# EVK-IRIS-W1-FC2_FC3_FC14_RMII.net
KiCad netlist of a schematic drawn in Altium Designer
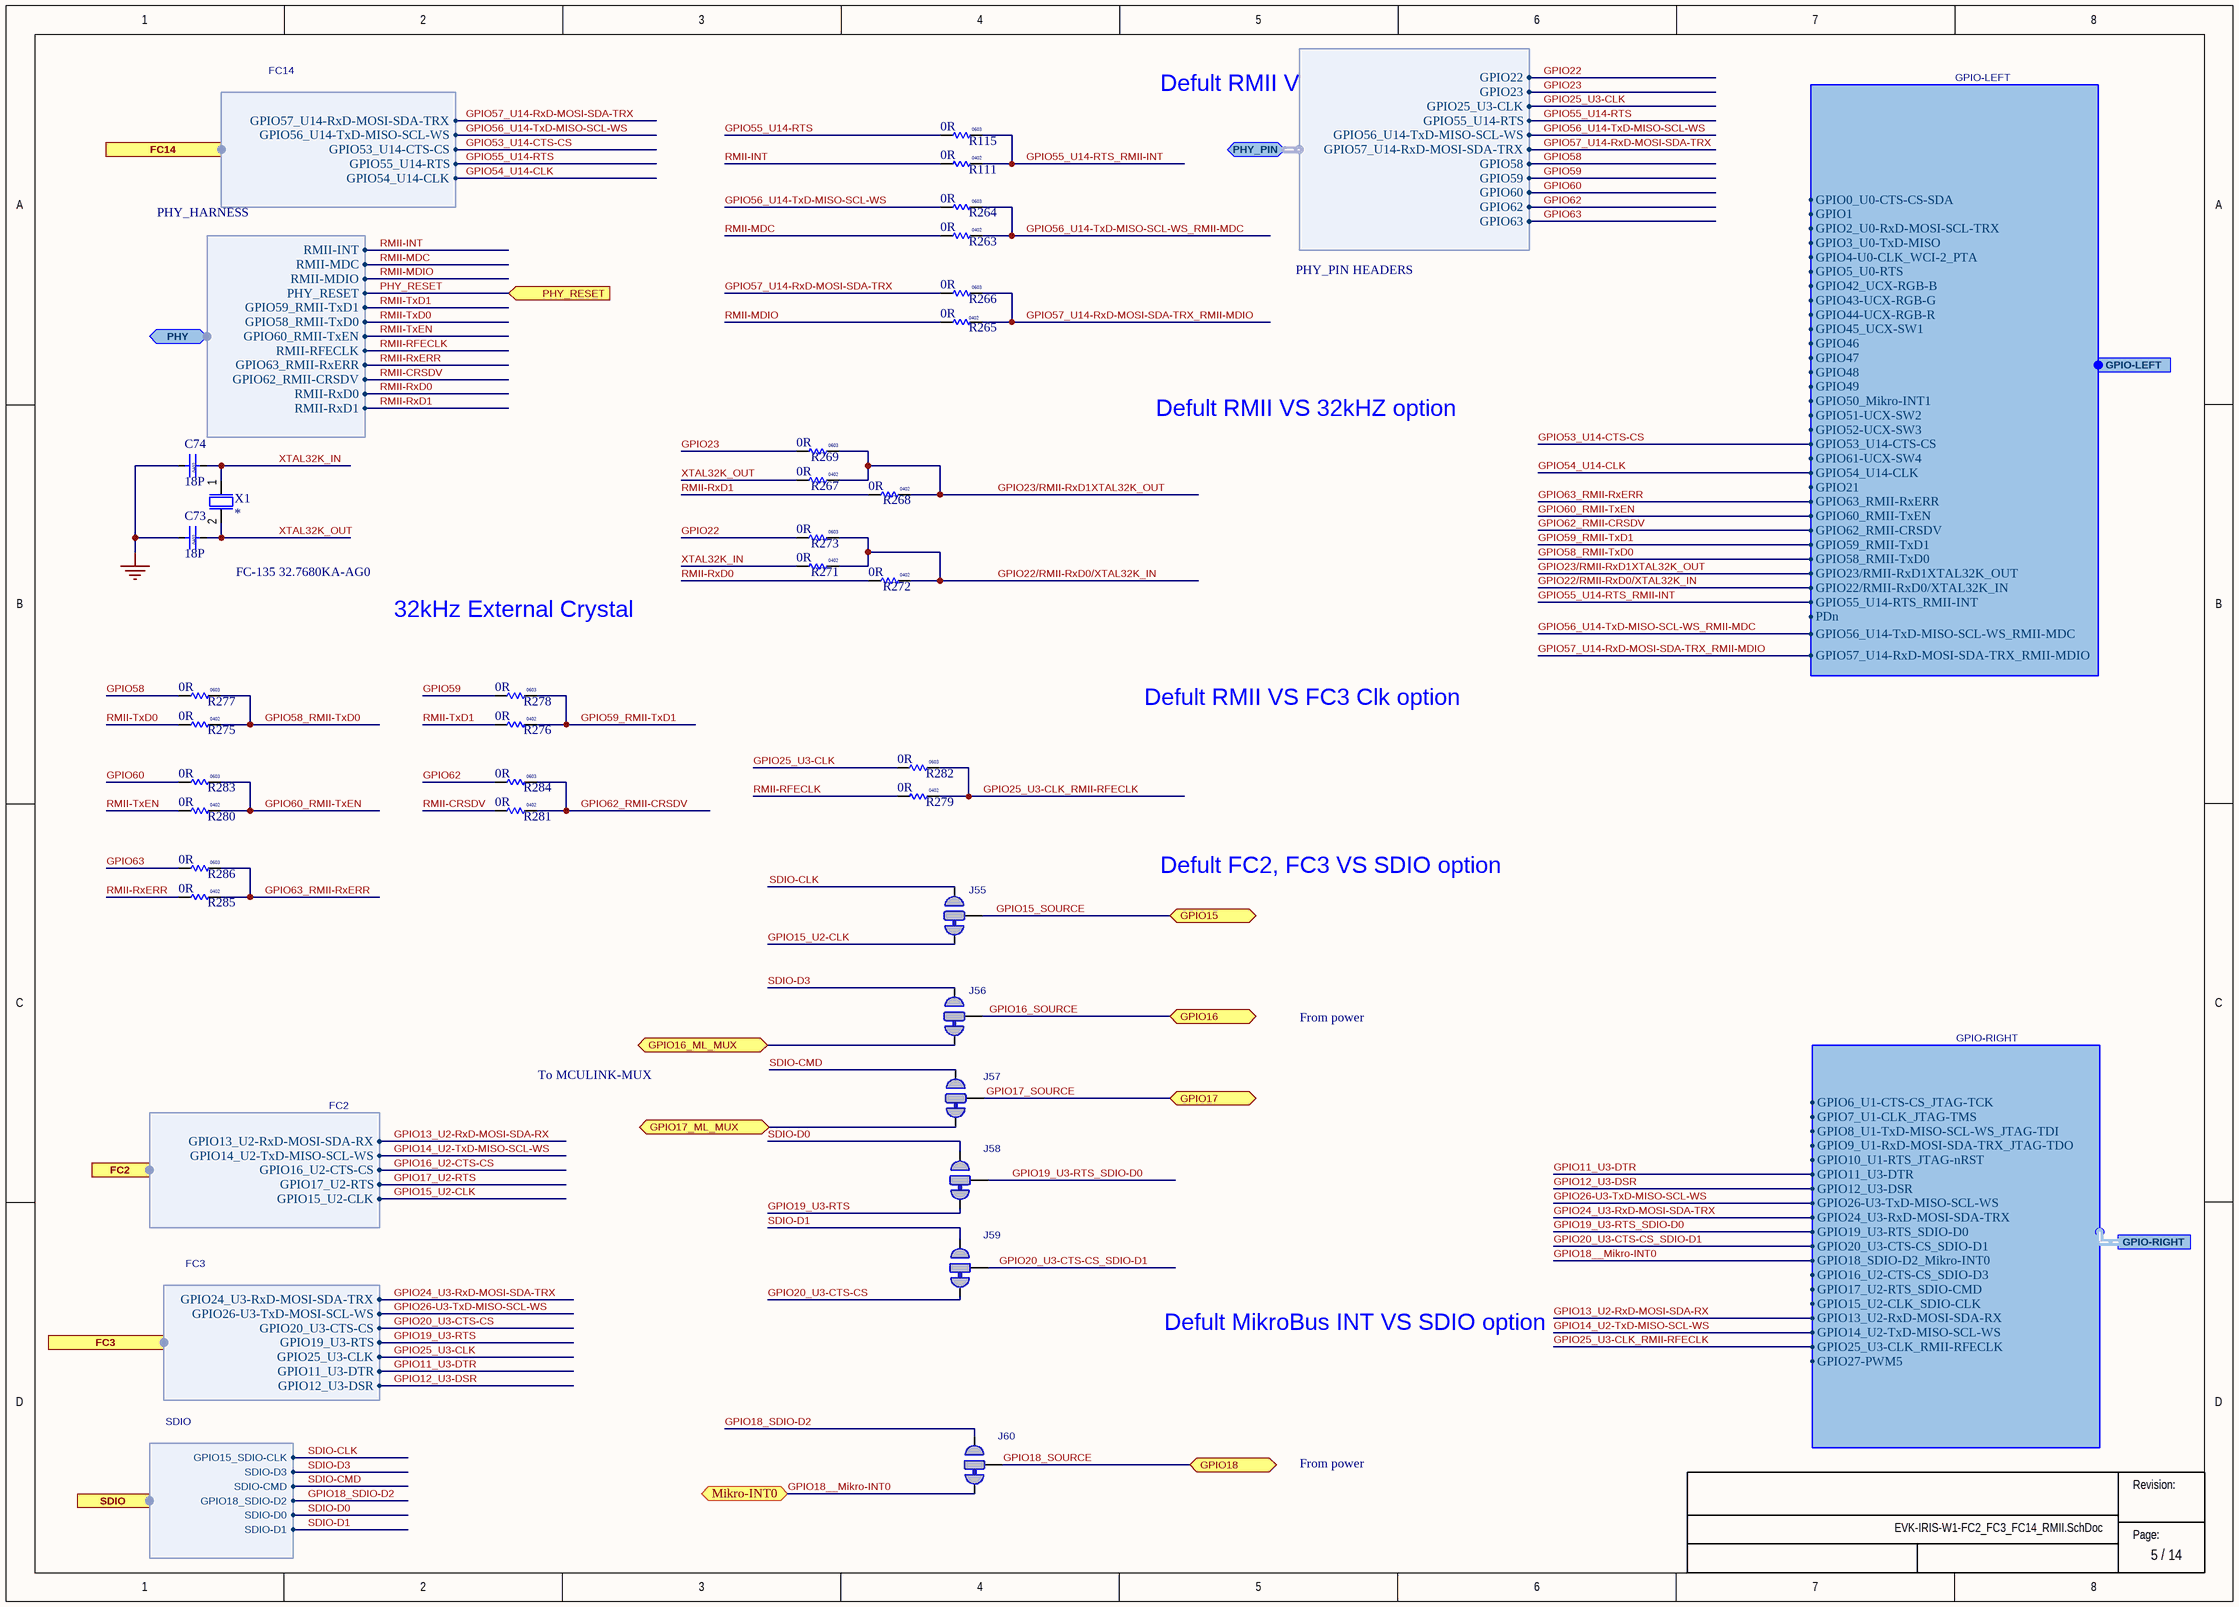
[diagram p0: EVK-IRIS-W1-FC2_FC3_FC14_RMII.SchDoc]

(export (version "E")
  (design (tool "Eeschema 10.0.6"))
  (components
    (comp (ref "C73")
      (value "18P")
      (footprint "Cap 0402")
      (description "CAP CER C0G 0402 18P 5% 25V")
      (fields
        (field (name "SIZE") "0402")
        (field (name "PART NUMBER") "UBXH01-0004017")
        (field (name "TOLERANCE") "5%")
        (field (name "EDITOR") "doris.zahnd")
        (field (name "RELEASED BY") "daniel.hurni")
      )
      (libsource (lib "UBX_Parts_DB_Lib") (part "Cap Chip"))
    )
    (comp (ref "C74")
      (value "18P")
      (footprint "Cap 0402")
      (description "CAP CER C0G 0402 18P 5% 25V")
      (fields
        (field (name "SIZE") "0402")
        (field (name "PART NUMBER") "UBXH01-0004017")
        (field (name "TOLERANCE") "5%")
        (field (name "EDITOR") "doris.zahnd")
        (field (name "RELEASED BY") "daniel.hurni")
      )
      (libsource (lib "UBX_Parts_DB_Lib") (part "Cap Chip"))
    )
    (comp (ref "J55")
      (value "Solderbridge-OptionDNP")
      (footprint "Solderbridge-Option")
      (description "Solderbridge-Option")
      (fields (field (name "ADDED BY") "Paul B"))
      (libsource (lib "PCB_Misc") (part "Solderbridge-Option"))
    )
    (comp (ref "J56")
      (value "Solderbridge-OptionDNP")
      (footprint "Solderbridge-Option")
      (description "Solderbridge-Option")
      (fields (field (name "ADDED BY") "Paul B"))
      (libsource (lib "PCB_Misc") (part "Solderbridge-Option"))
    )
    (comp (ref "J57")
      (value "Solderbridge-OptionDNP")
      (footprint "Solderbridge-Option")
      (description "Solderbridge-Option")
      (fields (field (name "ADDED BY") "Paul B"))
      (libsource (lib "PCB_Misc") (part "Solderbridge-Option"))
    )
    (comp (ref "J58")
      (value "Solderbridge-OptionDNP")
      (footprint "Solderbridge-Option")
      (description "Solderbridge-Option")
      (fields (field (name "ADDED BY") "Paul B"))
      (libsource (lib "PCB_Misc") (part "Solderbridge-Option"))
    )
    (comp (ref "J59")
      (value "Solderbridge-OptionDNP")
      (footprint "Solderbridge-Option")
      (description "Solderbridge-Option")
      (fields (field (name "ADDED BY") "Paul B"))
      (libsource (lib "PCB_Misc") (part "Solderbridge-Option"))
    )
    (comp (ref "J60")
      (value "Solderbridge-OptionDNP")
      (footprint "Solderbridge-Option")
      (description "Solderbridge-Option")
      (fields (field (name "ADDED BY") "Paul B"))
      (libsource (lib "PCB_Misc") (part "Solderbridge-Option"))
    )
    (comp (ref "R111")
      (value "0R")
      (footprint "RES 0402 HD")
      (description "RES THICK FILM CHIP 0402 0R 0 100mW")
      (fields
        (field (name "SIZE") "0402")
        (field (name "PART NUMBER") "UBXH18-0003002")
        (field (name "TOLERANCE") "0")
        (field (name "EDITOR") "charlotte.biber")
        (field (name "RELEASED BY") "peter.mueller")
      )
      (libsource (lib "UBX_Parts_DB_Lib") (part "Res sm"))
    )
    (comp (ref "R115")
      (value "0R")
      (footprint "RES 0603 HD")
      (description "RES THICK FILM CHIP 0603 0R 0 100mW")
      (fields
        (field (name "SIZE") "0603")
        (field (name "PART NUMBER") "UBXH18-0003001")
        (field (name "TOLERANCE") "0")
        (field (name "EDITOR") "martin.frauchiger")
        (field (name "RELEASED BY") "martin.frauchiger")
      )
      (libsource (lib "UBX_Parts_DB_Lib") (part "Res sm"))
    )
    (comp (ref "R263")
      (value "0R")
      (footprint "RES 0402 HD")
      (description "RES THICK FILM CHIP 0402 0R 0 100mW")
      (fields
        (field (name "SIZE") "0402")
        (field (name "PART NUMBER") "UBXH18-0003002")
        (field (name "TOLERANCE") "0")
        (field (name "EDITOR") "charlotte.biber")
        (field (name "RELEASED BY") "peter.mueller")
      )
      (libsource (lib "UBX_Parts_DB_Lib") (part "Res sm"))
    )
    (comp (ref "R264")
      (value "0R")
      (footprint "RES 0603 HD")
      (description "RES THICK FILM CHIP 0603 0R 0 100mW")
      (fields
        (field (name "SIZE") "0603")
        (field (name "PART NUMBER") "UBXH18-0003001")
        (field (name "TOLERANCE") "0")
        (field (name "EDITOR") "martin.frauchiger")
        (field (name "RELEASED BY") "martin.frauchiger")
      )
      (libsource (lib "UBX_Parts_DB_Lib") (part "Res sm"))
    )
    (comp (ref "R265")
      (value "0R")
      (footprint "RES 0402 HD")
      (description "RES THICK FILM CHIP 0402 0R 0 100mW")
      (fields
        (field (name "SIZE") "0402")
        (field (name "PART NUMBER") "UBXH18-0003002")
        (field (name "TOLERANCE") "0")
        (field (name "EDITOR") "charlotte.biber")
        (field (name "RELEASED BY") "peter.mueller")
      )
      (libsource (lib "UBX_Parts_DB_Lib") (part "Res sm"))
    )
    (comp (ref "R266")
      (value "0R")
      (footprint "RES 0603 HD")
      (description "RES THICK FILM CHIP 0603 0R 0 100mW")
      (fields
        (field (name "SIZE") "0603")
        (field (name "PART NUMBER") "UBXH18-0003001")
        (field (name "TOLERANCE") "0")
        (field (name "EDITOR") "martin.frauchiger")
        (field (name "RELEASED BY") "martin.frauchiger")
      )
      (libsource (lib "UBX_Parts_DB_Lib") (part "Res sm"))
    )
    (comp (ref "R267")
      (value "0R")
      (footprint "RES 0402 HD")
      (description "RES THICK FILM CHIP 0402 0R 0 100mW")
      (fields
        (field (name "SIZE") "0402")
        (field (name "PART NUMBER") "UBXH18-0003002")
        (field (name "TOLERANCE") "0")
        (field (name "EDITOR") "charlotte.biber")
        (field (name "RELEASED BY") "peter.mueller")
      )
      (libsource (lib "UBX_Parts_DB_Lib") (part "Res sm"))
    )
    (comp (ref "R268")
      (value "0R")
      (footprint "RES 0402 HD")
      (description "RES THICK FILM CHIP 0402 0R 0 100mW")
      (fields
        (field (name "SIZE") "0402")
        (field (name "PART NUMBER") "UBXH18-0003002")
        (field (name "TOLERANCE") "0")
        (field (name "EDITOR") "charlotte.biber")
        (field (name "RELEASED BY") "peter.mueller")
      )
      (libsource (lib "UBX_Parts_DB_Lib") (part "Res sm"))
    )
    (comp (ref "R269")
      (value "0R")
      (footprint "RES 0603 HD")
      (description "RES THICK FILM CHIP 0603 0R 0 100mW")
      (fields
        (field (name "SIZE") "0603")
        (field (name "PART NUMBER") "UBXH18-0003001")
        (field (name "TOLERANCE") "0")
        (field (name "EDITOR") "martin.frauchiger")
        (field (name "RELEASED BY") "martin.frauchiger")
      )
      (libsource (lib "UBX_Parts_DB_Lib") (part "Res sm"))
    )
    (comp (ref "R271")
      (value "0R")
      (footprint "RES 0402 HD")
      (description "RES THICK FILM CHIP 0402 0R 0 100mW")
      (fields
        (field (name "SIZE") "0402")
        (field (name "PART NUMBER") "UBXH18-0003002")
        (field (name "TOLERANCE") "0")
        (field (name "EDITOR") "charlotte.biber")
        (field (name "RELEASED BY") "peter.mueller")
      )
      (libsource (lib "UBX_Parts_DB_Lib") (part "Res sm"))
    )
    (comp (ref "R272")
      (value "0R")
      (footprint "RES 0402 HD")
      (description "RES THICK FILM CHIP 0402 0R 0 100mW")
      (fields
        (field (name "SIZE") "0402")
        (field (name "PART NUMBER") "UBXH18-0003002")
        (field (name "TOLERANCE") "0")
        (field (name "EDITOR") "charlotte.biber")
        (field (name "RELEASED BY") "peter.mueller")
      )
      (libsource (lib "UBX_Parts_DB_Lib") (part "Res sm"))
    )
    (comp (ref "R273")
      (value "0R")
      (footprint "RES 0603 HD")
      (description "RES THICK FILM CHIP 0603 0R 0 100mW")
      (fields
        (field (name "SIZE") "0603")
        (field (name "PART NUMBER") "UBXH18-0003001")
        (field (name "TOLERANCE") "0")
        (field (name "EDITOR") "martin.frauchiger")
        (field (name "RELEASED BY") "martin.frauchiger")
      )
      (libsource (lib "UBX_Parts_DB_Lib") (part "Res sm"))
    )
    (comp (ref "R275")
      (value "0R")
      (footprint "RES 0402 HD")
      (description "RES THICK FILM CHIP 0402 0R 0 100mW")
      (fields
        (field (name "SIZE") "0402")
        (field (name "PART NUMBER") "UBXH18-0003002")
        (field (name "TOLERANCE") "0")
        (field (name "EDITOR") "charlotte.biber")
        (field (name "RELEASED BY") "peter.mueller")
      )
      (libsource (lib "UBX_Parts_DB_Lib") (part "Res sm"))
    )
    (comp (ref "R276")
      (value "0R")
      (footprint "RES 0402 HD")
      (description "RES THICK FILM CHIP 0402 0R 0 100mW")
      (fields
        (field (name "SIZE") "0402")
        (field (name "PART NUMBER") "UBXH18-0003002")
        (field (name "TOLERANCE") "0")
        (field (name "EDITOR") "charlotte.biber")
        (field (name "RELEASED BY") "peter.mueller")
      )
      (libsource (lib "UBX_Parts_DB_Lib") (part "Res sm"))
    )
    (comp (ref "R277")
      (value "0R")
      (footprint "RES 0603 HD")
      (description "RES THICK FILM CHIP 0603 0R 0 100mW")
      (fields
        (field (name "SIZE") "0603")
        (field (name "PART NUMBER") "UBXH18-0003001")
        (field (name "TOLERANCE") "0")
        (field (name "EDITOR") "martin.frauchiger")
        (field (name "RELEASED BY") "martin.frauchiger")
      )
      (libsource (lib "UBX_Parts_DB_Lib") (part "Res sm"))
    )
    (comp (ref "R278")
      (value "0R")
      (footprint "RES 0603 HD")
      (description "RES THICK FILM CHIP 0603 0R 0 100mW")
      (fields
        (field (name "SIZE") "0603")
        (field (name "PART NUMBER") "UBXH18-0003001")
        (field (name "TOLERANCE") "0")
        (field (name "EDITOR") "martin.frauchiger")
        (field (name "RELEASED BY") "martin.frauchiger")
      )
      (libsource (lib "UBX_Parts_DB_Lib") (part "Res sm"))
    )
    (comp (ref "R279")
      (value "0R")
      (footprint "RES 0402 HD")
      (description "RES THICK FILM CHIP 0402 0R 0 100mW")
      (fields
        (field (name "SIZE") "0402")
        (field (name "PART NUMBER") "UBXH18-0003002")
        (field (name "TOLERANCE") "0")
        (field (name "EDITOR") "charlotte.biber")
        (field (name "RELEASED BY") "peter.mueller")
      )
      (libsource (lib "UBX_Parts_DB_Lib") (part "Res sm"))
    )
    (comp (ref "R280")
      (value "0R")
      (footprint "RES 0402 HD")
      (description "RES THICK FILM CHIP 0402 0R 0 100mW")
      (fields
        (field (name "SIZE") "0402")
        (field (name "PART NUMBER") "UBXH18-0003002")
        (field (name "TOLERANCE") "0")
        (field (name "EDITOR") "charlotte.biber")
        (field (name "RELEASED BY") "peter.mueller")
      )
      (libsource (lib "UBX_Parts_DB_Lib") (part "Res sm"))
    )
    (comp (ref "R281")
      (value "0R")
      (footprint "RES 0402 HD")
      (description "RES THICK FILM CHIP 0402 0R 0 100mW")
      (fields
        (field (name "SIZE") "0402")
        (field (name "PART NUMBER") "UBXH18-0003002")
        (field (name "TOLERANCE") "0")
        (field (name "EDITOR") "charlotte.biber")
        (field (name "RELEASED BY") "peter.mueller")
      )
      (libsource (lib "UBX_Parts_DB_Lib") (part "Res sm"))
    )
    (comp (ref "R282")
      (value "0R")
      (footprint "RES 0603 HD")
      (description "RES THICK FILM CHIP 0603 0R 0 100mW")
      (fields
        (field (name "SIZE") "0603")
        (field (name "PART NUMBER") "UBXH18-0003001")
        (field (name "TOLERANCE") "0")
        (field (name "EDITOR") "martin.frauchiger")
        (field (name "RELEASED BY") "martin.frauchiger")
      )
      (libsource (lib "UBX_Parts_DB_Lib") (part "Res sm"))
    )
    (comp (ref "R283")
      (value "0R")
      (footprint "RES 0603 HD")
      (description "RES THICK FILM CHIP 0603 0R 0 100mW")
      (fields
        (field (name "SIZE") "0603")
        (field (name "PART NUMBER") "UBXH18-0003001")
        (field (name "TOLERANCE") "0")
        (field (name "EDITOR") "martin.frauchiger")
        (field (name "RELEASED BY") "martin.frauchiger")
      )
      (libsource (lib "UBX_Parts_DB_Lib") (part "Res sm"))
    )
    (comp (ref "R284")
      (value "0R")
      (footprint "RES 0603 HD")
      (description "RES THICK FILM CHIP 0603 0R 0 100mW")
      (fields
        (field (name "SIZE") "0603")
        (field (name "PART NUMBER") "UBXH18-0003001")
        (field (name "TOLERANCE") "0")
        (field (name "EDITOR") "martin.frauchiger")
        (field (name "RELEASED BY") "martin.frauchiger")
      )
      (libsource (lib "UBX_Parts_DB_Lib") (part "Res sm"))
    )
    (comp (ref "R285")
      (value "0R")
      (footprint "RES 0402 HD")
      (description "RES THICK FILM CHIP 0402 0R 0 100mW")
      (fields
        (field (name "SIZE") "0402")
        (field (name "PART NUMBER") "UBXH18-0003002")
        (field (name "TOLERANCE") "0")
        (field (name "EDITOR") "charlotte.biber")
        (field (name "RELEASED BY") "peter.mueller")
      )
      (libsource (lib "UBX_Parts_DB_Lib") (part "Res sm"))
    )
    (comp (ref "R286")
      (value "0R")
      (footprint "RES 0603 HD")
      (description "RES THICK FILM CHIP 0603 0R 0 100mW")
      (fields
        (field (name "SIZE") "0603")
        (field (name "PART NUMBER") "UBXH18-0003001")
        (field (name "TOLERANCE") "0")
        (field (name "EDITOR") "martin.frauchiger")
        (field (name "RELEASED BY") "martin.frauchiger")
      )
      (libsource (lib "UBX_Parts_DB_Lib") (part "Res sm"))
    )
    (comp (ref "X1")
      (value "100-00005")
      (footprint "XTAL_3215")
      (description "XTAL, 2Pin, 32.768kHz, 7pF 20ppm")
      (fields (field (name "MANUFACTURER P/N") "*") (field (name "VOLTAGE") "None"))
      (libsource (lib "Arena_Parts_DB_Lib") (part "XTAL_2Pin"))
    )
  )
  (nets
    (net (code "14") (name "/GPIO15_SOURCE") (class "Default")
      (node (ref "J55") (pin "2") (pinfunction "2_2") (pintype "passive"))
    )
    (net (code "15") (name "/GPIO15_U2-CLK") (class "Default")
      (node (ref "J55") (pin "1") (pinfunction "1_1") (pintype "passive"))
    )
    (net (code "16") (name "/GPIO16_ML_MUX") (class "Default")
      (node (ref "J56") (pin "1") (pinfunction "1_1") (pintype "passive"))
    )
    (net (code "17") (name "/GPIO16_SOURCE") (class "Default")
      (node (ref "J56") (pin "2") (pinfunction "2_2") (pintype "passive"))
    )
    (net (code "19") (name "/GPIO17_ML_MUX") (class "Default")
      (node (ref "J57") (pin "1") (pinfunction "1_1") (pintype "passive"))
    )
    (net (code "20") (name "/GPIO17_SOURCE") (class "Default")
      (node (ref "J57") (pin "2") (pinfunction "2_2") (pintype "passive"))
    )
    (net (code "22") (name "/GPIO18_SDIO-D2") (class "Default")
      (node (ref "J60") (pin "3") (pinfunction "3_3") (pintype "passive"))
    )
    (net (code "23") (name "/GPIO18_SOURCE") (class "Default")
      (node (ref "J60") (pin "2") (pinfunction "2_2") (pintype "passive"))
    )
    (net (code "24") (name "/GPIO18__Mikro-INT0") (class "Default")
      (node (ref "J60") (pin "1") (pinfunction "1_1") (pintype "passive"))
    )
    (net (code "25") (name "/GPIO19_U3-RTS") (class "Default")
      (node (ref "J58") (pin "1") (pinfunction "1_1") (pintype "passive"))
    )
    (net (code "26") (name "/GPIO19_U3-RTS_SDIO-D0") (class "Default")
      (node (ref "J58") (pin "2") (pinfunction "2_2") (pintype "passive"))
    )
    (net (code "27") (name "/GPIO20_U3-CTS-CS") (class "Default")
      (node (ref "J59") (pin "1") (pinfunction "1_1") (pintype "passive"))
    )
    (net (code "28") (name "/GPIO20_U3-CTS-CS_SDIO-D1") (class "Default")
      (node (ref "J59") (pin "2") (pinfunction "2_2") (pintype "passive"))
    )
    (net (code "29") (name "/GPIO22") (class "Default")
      (node (ref "R273") (pin "1") (pinfunction "1_1") (pintype "passive"))
    )
    (net (code "30") (name "/GPIO22{slash}RMII-RxD0{slash}XTAL32K_IN") (class "Default")
      (node (ref "R271") (pin "2") (pinfunction "2_2") (pintype "passive"))
      (node (ref "R272") (pin "2") (pinfunction "2_2") (pintype "passive"))
      (node (ref "R273") (pin "2") (pinfunction "2_2") (pintype "passive"))
    )
    (net (code "31") (name "/GPIO23") (class "Default")
      (node (ref "R269") (pin "1") (pinfunction "1_1") (pintype "passive"))
    )
    (net (code "32") (name "/GPIO23{slash}RMII-RxD1XTAL32K_OUT") (class "Default")
      (node (ref "R267") (pin "2") (pinfunction "2_2") (pintype "passive"))
      (node (ref "R268") (pin "2") (pinfunction "2_2") (pintype "passive"))
      (node (ref "R269") (pin "2") (pinfunction "2_2") (pintype "passive"))
    )
    (net (code "34") (name "/GPIO25_U3-CLK") (class "Default")
      (node (ref "R282") (pin "1") (pinfunction "1_1") (pintype "passive"))
    )
    (net (code "35") (name "/GPIO25_U3-CLK_RMII-RFECLK") (class "Default")
      (node (ref "R279") (pin "2") (pinfunction "2_2") (pintype "passive"))
      (node (ref "R282") (pin "2") (pinfunction "2_2") (pintype "passive"))
    )
    (net (code "39") (name "/GPIO55_U14-RTS") (class "Default")
      (node (ref "R115") (pin "1") (pinfunction "1_1") (pintype "passive"))
    )
    (net (code "40") (name "/GPIO55_U14-RTS_RMII-INT") (class "Default")
      (node (ref "R111") (pin "2") (pinfunction "2_2") (pintype "passive"))
      (node (ref "R115") (pin "2") (pinfunction "2_2") (pintype "passive"))
    )
    (net (code "41") (name "/GPIO56_U14-TxD-MISO-SCL-WS") (class "Default")
      (node (ref "R264") (pin "1") (pinfunction "1_1") (pintype "passive"))
    )
    (net (code "42") (name "/GPIO56_U14-TxD-MISO-SCL-WS_RMII-MDC") (class "Default")
      (node (ref "R263") (pin "2") (pinfunction "2_2") (pintype "passive"))
      (node (ref "R264") (pin "2") (pinfunction "2_2") (pintype "passive"))
    )
    (net (code "43") (name "/GPIO57_U14-RxD-MOSI-SDA-TRX") (class "Default")
      (node (ref "R266") (pin "1") (pinfunction "1_1") (pintype "passive"))
    )
    (net (code "44") (name "/GPIO57_U14-RxD-MOSI-SDA-TRX_RMII-MDIO") (class "Default")
      (node (ref "R265") (pin "2") (pinfunction "2_2") (pintype "passive"))
      (node (ref "R266") (pin "2") (pinfunction "2_2") (pintype "passive"))
    )
    (net (code "45") (name "/GPIO58") (class "Default")
      (node (ref "R277") (pin "1") (pinfunction "1_1") (pintype "passive"))
    )
    (net (code "46") (name "/GPIO58_RMII-TxD0") (class "Default")
      (node (ref "R275") (pin "2") (pinfunction "2_2") (pintype "passive"))
      (node (ref "R277") (pin "2") (pinfunction "2_2") (pintype "passive"))
    )
    (net (code "47") (name "/GPIO59") (class "Default")
      (node (ref "R278") (pin "1") (pinfunction "1_1") (pintype "passive"))
    )
    (net (code "48") (name "/GPIO59_RMII-TxD1") (class "Default")
      (node (ref "R276") (pin "2") (pinfunction "2_2") (pintype "passive"))
      (node (ref "R278") (pin "2") (pinfunction "2_2") (pintype "passive"))
    )
    (net (code "49") (name "/GPIO60") (class "Default")
      (node (ref "R283") (pin "1") (pinfunction "1_1") (pintype "passive"))
    )
    (net (code "50") (name "/GPIO60_RMII-TxEN") (class "Default")
      (node (ref "R280") (pin "2") (pinfunction "2_2") (pintype "passive"))
      (node (ref "R283") (pin "2") (pinfunction "2_2") (pintype "passive"))
    )
    (net (code "51") (name "/GPIO62") (class "Default")
      (node (ref "R284") (pin "1") (pinfunction "1_1") (pintype "passive"))
    )
    (net (code "52") (name "/GPIO62_RMII-CRSDV") (class "Default")
      (node (ref "R281") (pin "2") (pinfunction "2_2") (pintype "passive"))
      (node (ref "R284") (pin "2") (pinfunction "2_2") (pintype "passive"))
    )
    (net (code "53") (name "/GPIO63") (class "Default")
      (node (ref "R286") (pin "1") (pinfunction "1_1") (pintype "passive"))
    )
    (net (code "54") (name "/GPIO63_RMII-RxERR") (class "Default")
      (node (ref "R285") (pin "2") (pinfunction "2_2") (pintype "passive"))
      (node (ref "R286") (pin "2") (pinfunction "2_2") (pintype "passive"))
    )
    (net (code "56") (name "/RMII-CRSDV") (class "Default")
      (node (ref "R281") (pin "1") (pinfunction "1_1") (pintype "passive"))
    )
    (net (code "57") (name "/RMII-INT") (class "Default")
      (node (ref "R111") (pin "1") (pinfunction "1_1") (pintype "passive"))
    )
    (net (code "58") (name "/RMII-MDC") (class "Default")
      (node (ref "R263") (pin "1") (pinfunction "1_1") (pintype "passive"))
    )
    (net (code "59") (name "/RMII-MDIO") (class "Default")
      (node (ref "R265") (pin "1") (pinfunction "1_1") (pintype "passive"))
    )
    (net (code "60") (name "/RMII-RFECLK") (class "Default")
      (node (ref "R279") (pin "1") (pinfunction "1_1") (pintype "passive"))
    )
    (net (code "61") (name "/RMII-RxD0") (class "Default")
      (node (ref "R272") (pin "1") (pinfunction "1_1") (pintype "passive"))
    )
    (net (code "62") (name "/RMII-RxD1") (class "Default")
      (node (ref "R268") (pin "1") (pinfunction "1_1") (pintype "passive"))
    )
    (net (code "63") (name "/RMII-RxERR") (class "Default")
      (node (ref "R285") (pin "1") (pinfunction "1_1") (pintype "passive"))
    )
    (net (code "64") (name "/RMII-TxD0") (class "Default")
      (node (ref "R275") (pin "1") (pinfunction "1_1") (pintype "passive"))
    )
    (net (code "65") (name "/RMII-TxD1") (class "Default")
      (node (ref "R276") (pin "1") (pinfunction "1_1") (pintype "passive"))
    )
    (net (code "66") (name "/RMII-TxEN") (class "Default")
      (node (ref "R280") (pin "1") (pinfunction "1_1") (pintype "passive"))
    )
    (net (code "67") (name "/SDIO-CLK") (class "Default")
      (node (ref "J55") (pin "3") (pinfunction "3_3") (pintype "passive"))
    )
    (net (code "68") (name "/SDIO-CMD") (class "Default")
      (node (ref "J57") (pin "3") (pinfunction "3_3") (pintype "passive"))
    )
    (net (code "69") (name "/SDIO-D0") (class "Default")
      (node (ref "J58") (pin "3") (pinfunction "3_3") (pintype "passive"))
    )
    (net (code "70") (name "/SDIO-D1") (class "Default")
      (node (ref "J59") (pin "3") (pinfunction "3_3") (pintype "passive"))
    )
    (net (code "71") (name "/SDIO-D3") (class "Default")
      (node (ref "J56") (pin "3") (pinfunction "3_3") (pintype "passive"))
    )
    (net (code "72") (name "/XTAL32K_IN") (class "Default")
      (node (ref "C74") (pin "1") (pinfunction "1_1") (pintype "passive"))
      (node (ref "R271") (pin "1") (pinfunction "1_1") (pintype "passive"))
      (node (ref "X1") (pin "1") (pintype "passive"))
    )
    (net (code "73") (name "/XTAL32K_OUT") (class "Default")
      (node (ref "C73") (pin "1") (pinfunction "1_1") (pintype "passive"))
      (node (ref "R267") (pin "1") (pinfunction "1_1") (pintype "passive"))
      (node (ref "X1") (pin "2") (pintype "passive"))
    )
    (net (code "82") (name "GND") (class "Default")
      (node (ref "C73") (pin "2") (pinfunction "2_2") (pintype "passive"))
      (node (ref "C74") (pin "2") (pinfunction "2_2") (pintype "passive"))
    )
  )
)
